# PSU.net
KiCad netlist of a schematic drawn in EAGLE
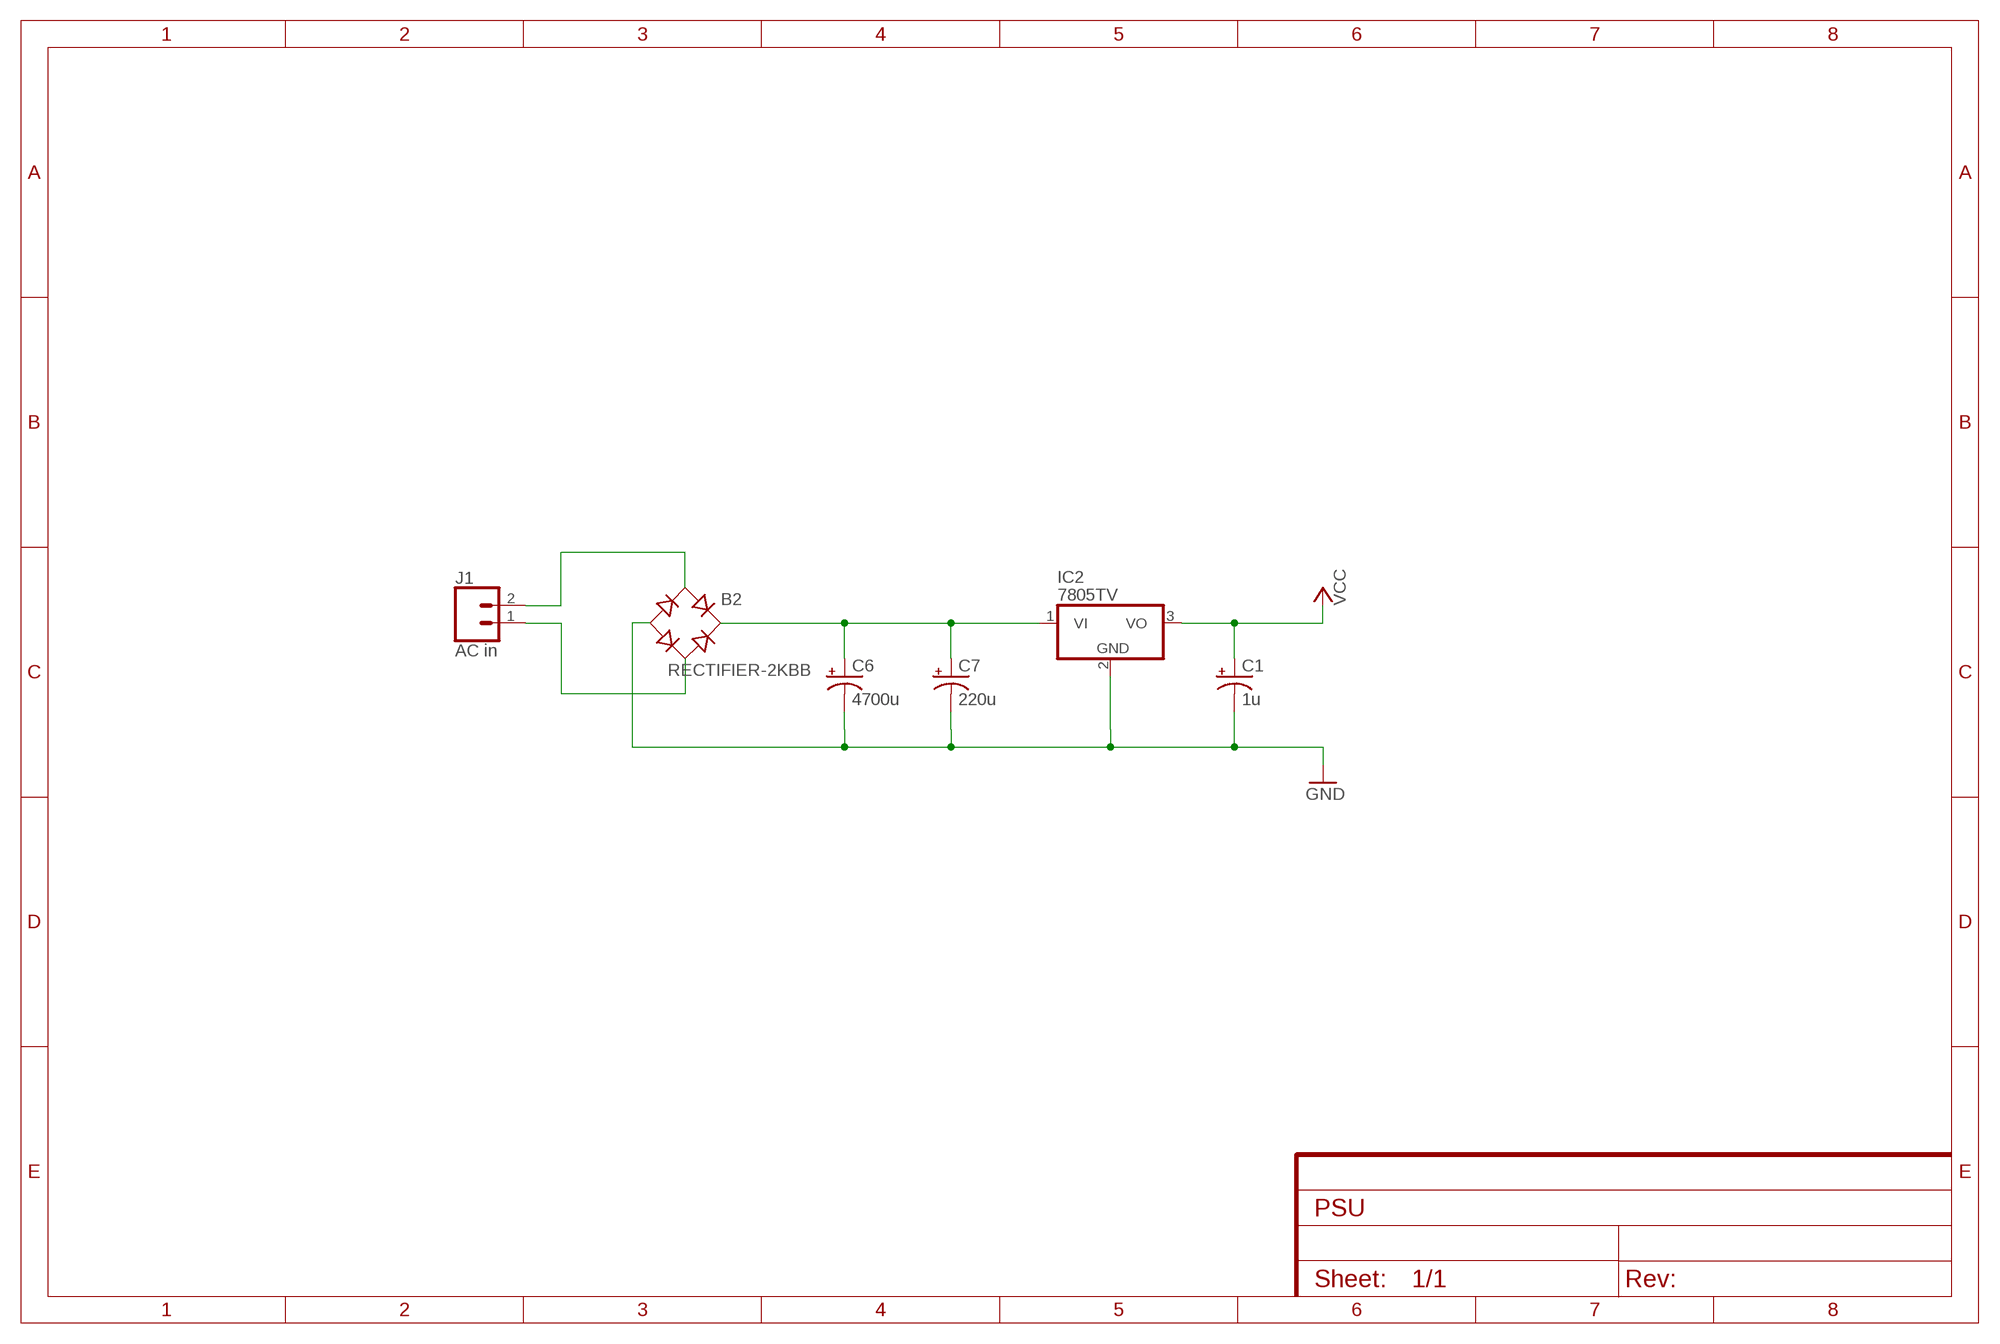
[diagram p0: schematic, sheet 1]

(export (version "E")
  (design (tool "Eeschema 10.0.6"))
  (components
    (comp (ref "B2")
      (value "RECTIFIER-2KBB")
      (footprint "eagle-import:2KBB")
      (libsource (lib "eagle-import") (part "RECTIFIER-2KBB"))
    )
    (comp (ref "C1")
      (value "1u")
      (footprint "eagle-import:E2,5-5")
      (libsource (lib "eagle-import") (part "CPOL-USE2.5-5"))
    )
    (comp (ref "C6")
      (value "4700u")
      (footprint "eagle-import:E7,5-16")
      (libsource (lib "eagle-import") (part "CPOL-USE7.5-16"))
    )
    (comp (ref "C7")
      (value "220u")
      (footprint "eagle-import:E2,5-6")
      (libsource (lib "eagle-import") (part "CPOL-USE2.5-6"))
    )
    (comp (ref "IC2")
      (value "7805TV")
      (footprint "eagle-import:TO220V")
      (libsource (lib "eagle-import") (part "78TV05"))
    )
    (comp (ref "J1")
      (value "AC in")
      (footprint "eagle-import:1X02")
      (libsource (lib "eagle-import") (part "CONN_02"))
    )
  )
  (nets
    (net (code "1") (name "GND") (class "Default")
      (node (ref "B2") (pin "-") (pinfunction "-_-") (pintype "passive"))
      (node (ref "C1") (pin "-") (pinfunction "-_-") (pintype "passive"))
      (node (ref "C6") (pin "-") (pinfunction "-_-") (pintype "passive"))
      (node (ref "C7") (pin "-") (pinfunction "-_-") (pintype "passive"))
      (node (ref "IC2") (pin "2") (pinfunction "GND_2") (pintype "passive"))
    )
    (net (code "2") (name "Net-(B2-PadAC1)") (class "Default")
      (node (ref "B2") (pin "AC1") (pinfunction "AC1_AC1") (pintype "passive"))
      (node (ref "J1") (pin "2") (pinfunction "2_2") (pintype "passive"))
    )
    (net (code "3") (name "Net-(B2-PadAC2)") (class "Default")
      (node (ref "B2") (pin "AC2") (pinfunction "AC2_AC2") (pintype "passive"))
      (node (ref "J1") (pin "1") (pinfunction "1_1") (pintype "passive"))
    )
    (net (code "4") (name "Net-(IC2-VI)") (class "Default")
      (node (ref "B2") (pin "+") (pinfunction "+_+") (pintype "passive"))
      (node (ref "C6") (pin "+") (pinfunction "+_+") (pintype "passive"))
      (node (ref "C7") (pin "+") (pinfunction "+_+") (pintype "passive"))
      (node (ref "IC2") (pin "1") (pinfunction "VI_1") (pintype "input"))
    )
    (net (code "5") (name "VCC") (class "Default")
      (node (ref "C1") (pin "+") (pinfunction "+_+") (pintype "passive"))
      (node (ref "IC2") (pin "3") (pinfunction "VO_3") (pintype "passive"))
    )
  )
)
